# DS18B20U_Module_Schematic.net
KiCad netlist of a schematic drawn in Altium Designer
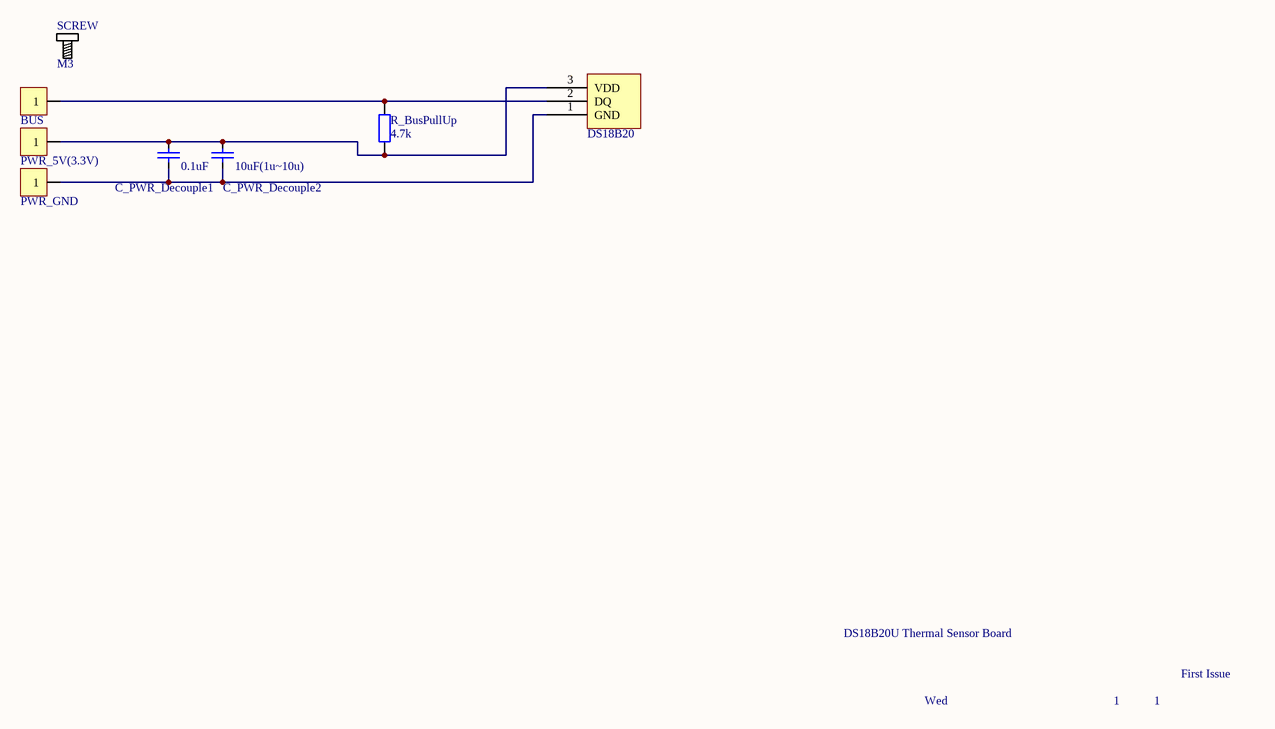
[diagram p0: DS18B20U Module Schematic.SchDoc]

(export (version "E")
  (design (tool "Eeschema 10.0.6"))
  (components
    (comp (ref "BUS")
      (value "HDR1X1_180_2.54")
      (footprint "PCB_Connector:HDR1X1_180_2.54")
      (description "Header")
      (libsource (lib "SCH_Connector") (part "HDR1X1_180_2.54"))
    )
    (comp (ref "C_PWR_Decouple1")
      (value "0.1uF")
      (footprint "PCB_Passive:CAP_0603")
      (description "Capacitor")
      (fields (field (name "Comment") "Cap_0603"))
      (libsource (lib "SCH_Passive") (part "Cap_0603"))
    )
    (comp (ref "C_PWR_Decouple2")
      (value "10uF(1u~10u)")
      (footprint "PCB_Passive:CAP_0603")
      (description "Capacitor")
      (fields (field (name "Comment") "Cap_0603"))
      (libsource (lib "SCH_Passive") (part "Cap_0603"))
    )
    (comp (ref "DS18B20")
      (value "DS18B20")
      (footprint "DS18B20U Module:TO-92")
      (description "DS18B20 TO-92")
      (libsource (lib "DS18B20U Module") (part "DS18B20 TO-92"))
    )
    (comp (ref "PWR_5V(3.3V)")
      (value "HDR1X1_180_2.54")
      (footprint "PCB_Connector:HDR1X1_180_2.54")
      (description "Header")
      (libsource (lib "SCH_Connector") (part "HDR1X1_180_2.54"))
    )
    (comp (ref "PWR_GND")
      (value "HDR1X1_180_2.54")
      (footprint "PCB_Connector:HDR1X1_180_2.54")
      (description "Header")
      (libsource (lib "SCH_Connector") (part "HDR1X1_180_2.54"))
    )
    (comp (ref "R_BusPullUp")
      (value "4.7k")
      (footprint "PCB_Passive:RES_0603")
      (description "Resistor")
      (fields (field (name "Comment") "Res_0603"))
      (libsource (lib "SCH_Passive") (part "Res_0603"))
    )
    (comp (ref "SCREW")
      (value "M3")
      (footprint "Relay Module:SCRREW_M3")
      (description "Screw")
      (libsource (lib "Relay Module") (part "Screw_M3"))
    )
  )
  (nets
    (net (code "1") (name "Net-(DS18B20-DQ)") (class "Default")
      (node (ref "BUS") (pin "1") (pinfunction "1_1") (pintype "passive"))
      (node (ref "DS18B20") (pin "2") (pinfunction "DQ_2") (pintype "passive"))
      (node (ref "R_BusPullUp") (pin "2") (pinfunction "2_2") (pintype "passive"))
    )
    (net (code "2") (name "Net-(DS18B20-GND)") (class "Default")
      (node (ref "C_PWR_Decouple1") (pin "1") (pinfunction "1_1") (pintype "passive"))
      (node (ref "C_PWR_Decouple2") (pin "1") (pinfunction "1_1") (pintype "passive"))
      (node (ref "DS18B20") (pin "1") (pinfunction "GND_1") (pintype "passive"))
      (node (ref "PWR_GND") (pin "1") (pinfunction "1_1") (pintype "passive"))
    )
    (net (code "3") (name "Net-(DS18B20-VDD)") (class "Default")
      (node (ref "C_PWR_Decouple1") (pin "2") (pinfunction "2_2") (pintype "passive"))
      (node (ref "C_PWR_Decouple2") (pin "2") (pinfunction "2_2") (pintype "passive"))
      (node (ref "DS18B20") (pin "3") (pinfunction "VDD_3") (pintype "passive"))
      (node (ref "PWR_5V(3.3V)") (pin "1") (pinfunction "1_1") (pintype "passive"))
      (node (ref "R_BusPullUp") (pin "1") (pinfunction "1_1") (pintype "passive"))
    )
  )
)
